# Receiver_Ckt.net
KiCad netlist of a schematic drawn in EAGLE
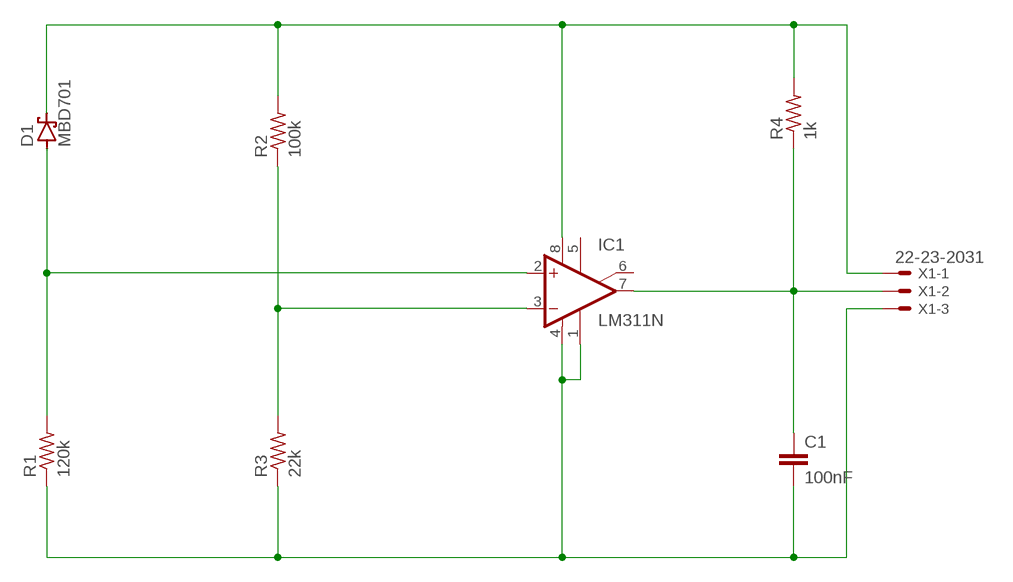
[diagram p0: schematic, sheet 1]

(export (version "E")
  (design (tool "Eeschema 10.0.6"))
  (components
    (comp (ref "C1")
      (value "100nF")
      (footprint "eagle-import:C0603")
      (libsource (lib "eagle-import") (part "C-EUC0603"))
    )
    (comp (ref "D1")
      (value "MBD701")
      (footprint "eagle-import:TO92H")
      (libsource (lib "eagle-import") (part "MBD701"))
    )
    (comp (ref "IC1")
      (value "LM311N")
      (footprint "eagle-import:DIL08")
      (libsource (lib "eagle-import") (part "LM311N"))
    )
    (comp (ref "R1")
      (value "120k")
      (footprint "eagle-import:R0603")
      (libsource (lib "eagle-import") (part "R-US_R0603"))
    )
    (comp (ref "R2")
      (value "100k")
      (footprint "eagle-import:R0603")
      (libsource (lib "eagle-import") (part "R-US_R0603"))
    )
    (comp (ref "R3")
      (value "22k")
      (footprint "eagle-import:R0603")
      (libsource (lib "eagle-import") (part "R-US_R0603"))
    )
    (comp (ref "R4")
      (value "1k")
      (footprint "eagle-import:R0603")
      (libsource (lib "eagle-import") (part "R-US_R0603"))
    )
    (comp (ref "X1")
      (value "22-23-2031")
      (footprint "eagle-import:22-23-2031")
      (fields (field (name "MF") "MOLEX"))
      (libsource (lib "eagle-import") (part "22-23-2031"))
    )
  )
  (nets
    (net (code "1") (name "Net-(D1-A)") (class "Default")
      (node (ref "D1") (pin "1") (pinfunction "A_1") (pintype "passive"))
      (node (ref "IC1") (pin "2") (pinfunction "+IN_2") (pintype "input"))
      (node (ref "R1") (pin "2") (pinfunction "2_2") (pintype "passive"))
    )
    (net (code "2") (name "Net-(D1-C)") (class "Default")
      (node (ref "D1") (pin "2") (pinfunction "C_2") (pintype "passive"))
      (node (ref "IC1") (pin "8") (pinfunction "V+_8") (pintype "power_in"))
      (node (ref "R2") (pin "2") (pinfunction "2_2") (pintype "passive"))
      (node (ref "R4") (pin "2") (pinfunction "2_2") (pintype "passive"))
      (node (ref "X1") (pin "1") (pinfunction "S_1") (pintype "passive"))
    )
    (net (code "3") (name "Net-(IC1--IN)") (class "Default")
      (node (ref "IC1") (pin "3") (pinfunction "-IN_3") (pintype "input"))
      (node (ref "R2") (pin "1") (pinfunction "1_1") (pintype "passive"))
      (node (ref "R3") (pin "2") (pinfunction "2_2") (pintype "passive"))
    )
    (net (code "4") (name "Net-(IC1-GND)") (class "Default")
      (node (ref "C1") (pin "2") (pinfunction "2_2") (pintype "passive"))
      (node (ref "IC1") (pin "1") (pinfunction "GND_1") (pintype "passive"))
      (node (ref "IC1") (pin "4") (pinfunction "V-_4") (pintype "power_in"))
      (node (ref "R1") (pin "1") (pinfunction "1_1") (pintype "passive"))
      (node (ref "R3") (pin "1") (pinfunction "1_1") (pintype "passive"))
      (node (ref "X1") (pin "3") (pinfunction "S_3") (pintype "passive"))
    )
    (net (code "5") (name "Net-(IC1-OUT)") (class "Default")
      (node (ref "C1") (pin "1") (pinfunction "1_1") (pintype "passive"))
      (node (ref "IC1") (pin "7") (pinfunction "OUT_7") (pintype "output"))
      (node (ref "R4") (pin "1") (pinfunction "1_1") (pintype "passive"))
      (node (ref "X1") (pin "2") (pinfunction "S_2") (pintype "passive"))
    )
    (net (code "6") (name "unconnected-(IC1-ON-Pad5)") (class "Default")
      (node (ref "IC1") (pin "5") (pinfunction "ON_5") (pintype "passive"))
    )
    (net (code "7") (name "unconnected-(IC1-ON{slash}STR-Pad6)") (class "Default")
      (node (ref "IC1") (pin "6") (pinfunction "ON/STR_6") (pintype "passive"))
    )
  )
)
